# Wiring.net
KiCad netlist of a schematic drawn in Altium Designer
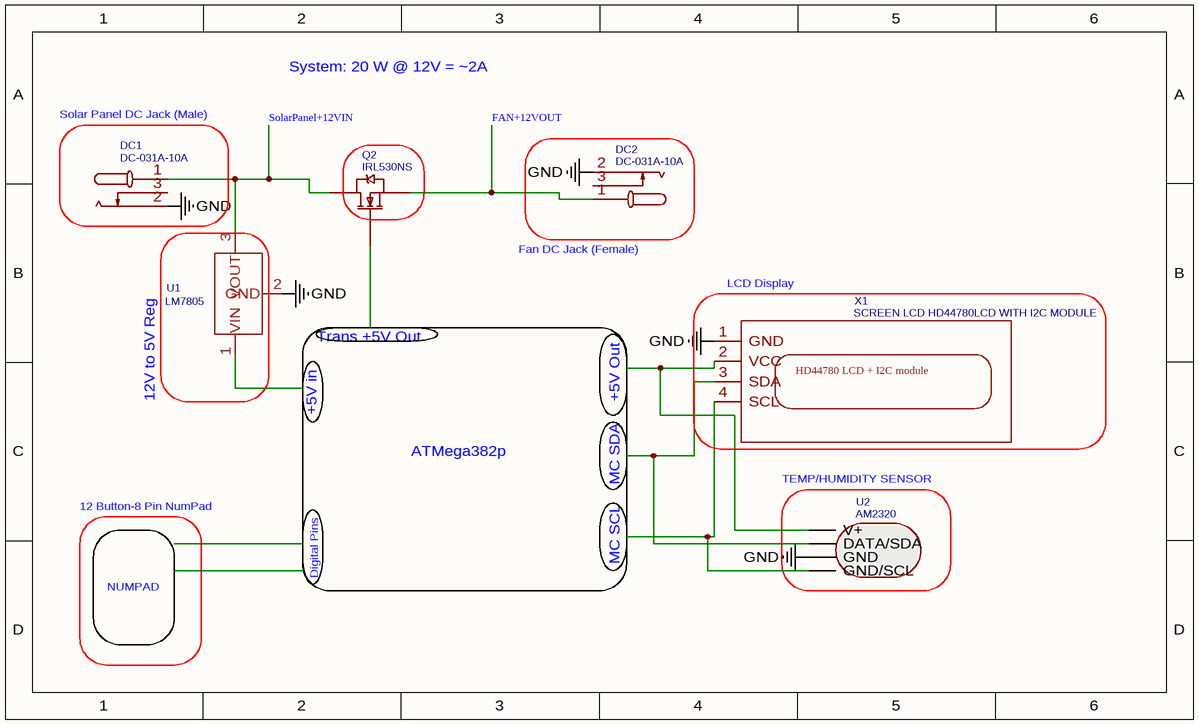
[diagram p0: Wiring.schdoc]

(export (version "E")
  (design (tool "Eeschema 10.0.6"))
  (components
    (comp (ref "DC1")
      (value "DC-031A-10A")
      (footprint "DC-IN-SMD_DC-031A-10A")
      (fields (field (name "BOM_SUPPLIER PART") "C145927") (field (name "CONTRIBUTOR") "LCSC"))
      (libsource (lib "altium-import") (part "root_0_DC-031A-10A_"))
    )
    (comp (ref "DC2")
      (value "DC-031A-10A")
      (footprint "DC-IN-SMD_DC-031A-10A")
      (fields (field (name "BOM_SUPPLIER PART") "C145927") (field (name "CONTRIBUTOR") "LCSC"))
      (libsource (lib "altium-import") (part "root_2_DC-031A-10A_"))
    )
    (comp (ref "Q2")
      (value "IRL530NS")
      (footprint "D2PAK")
      (libsource (lib "altium-import") (part "root_1_IRL530NS_"))
    )
    (comp (ref "U1")
      (value "LM7805")
      (footprint "SEEED-TO-220")
      (fields
        (field (name "BOM_SUPPLIER PART") "310030049")
        (field (name "BOM_MANUFACTURER PART") "LM7805ACT")
      )
      (libsource (lib "altium-import") (part "root_1_LM7805_"))
    )
    (comp (ref "U2")
      (value "AM2320")
      (footprint "AM2320")
      (fields
        (field (name "BOM_SUPPLIER PART") "E59481")
        (field (name "BOM_MANUFACTURER PART") "Header-Male-2.54_1x4")
      )
      (libsource (lib "altium-import") (part "root_0_AM2320_"))
    )
    (comp (ref "X1")
      (value "SCREEN LCD HD44780LCD WITH I2C MODULE")
      (footprint "LCD HD44780LCD WITH I2C MODULE")
      (fields (field (name "CONTRIBUTOR") "dartagnan586e"))
      (libsource (lib "altium-import") (part "root_0_SCREEN LCD HD44780LCD WITH I2C MODULE_"))
    )
  )
  (nets
    (net (code "1") (name "/FAN+12VOUT") (class "Default")
      (node (ref "DC2") (pin "1") (pinfunction "1_1") (pintype "passive"))
      (node (ref "Q2") (pin "3") (pinfunction "S_3") (pintype "passive"))
    )
    (net (code "2") (name "/SolarPanel+12VIN") (class "Default")
      (node (ref "DC1") (pin "1") (pinfunction "1_1") (pintype "passive"))
      (node (ref "Q2") (pin "2") (pinfunction "D_2") (pintype "passive"))
      (node (ref "U1") (pin "3") (pinfunction "VOUT_3") (pintype "passive"))
    )
    (net (code "3") (name "GND") (class "Default")
      (node (ref "DC1") (pin "2") (pinfunction "2_2") (pintype "passive"))
      (node (ref "DC2") (pin "2") (pinfunction "2_2") (pintype "passive"))
      (node (ref "U1") (pin "2") (pinfunction "GND_2") (pintype "passive"))
      (node (ref "U2") (pin "3") (pinfunction "GND_3") (pintype "passive"))
      (node (ref "X1") (pin "1") (pinfunction "GND_1") (pintype "passive"))
    )
    (net (code "4") (name "Net-(U2-DATA{slash}SDA)") (class "Default")
      (node (ref "U2") (pin "2") (pinfunction "DATA/SDA_2") (pintype "passive"))
      (node (ref "X1") (pin "3") (pinfunction "SDA_3") (pintype "passive"))
    )
    (net (code "5") (name "Net-(U2-GND{slash}SCL)") (class "Default")
      (node (ref "U2") (pin "4") (pinfunction "GND/SCL_4") (pintype "passive"))
      (node (ref "X1") (pin "4") (pinfunction "SCL_4") (pintype "passive"))
    )
    (net (code "6") (name "Net-(U2-V+)") (class "Default")
      (node (ref "U2") (pin "1") (pinfunction "V+_1") (pintype "passive"))
      (node (ref "X1") (pin "2") (pinfunction "VCC_2") (pintype "passive"))
    )
    (net (code "7") (name "unconnected-(DC1-Pad3)") (class "Default")
      (node (ref "DC1") (pin "3") (pinfunction "3_3") (pintype "passive"))
    )
    (net (code "8") (name "unconnected-(DC2-Pad3)") (class "Default")
      (node (ref "DC2") (pin "3") (pinfunction "3_3") (pintype "passive"))
    )
    (net (code "9") (name "unconnected-(Q2-G-Pad1)") (class "Default")
      (node (ref "Q2") (pin "1") (pinfunction "G_1") (pintype "passive"))
    )
    (net (code "10") (name "unconnected-(U1-VIN-Pad1)") (class "Default")
      (node (ref "U1") (pin "1") (pinfunction "VIN_1") (pintype "passive"))
    )
  )
)
